# sfpp_conn.net
KiCad netlist of a schematic drawn in Altium Designer
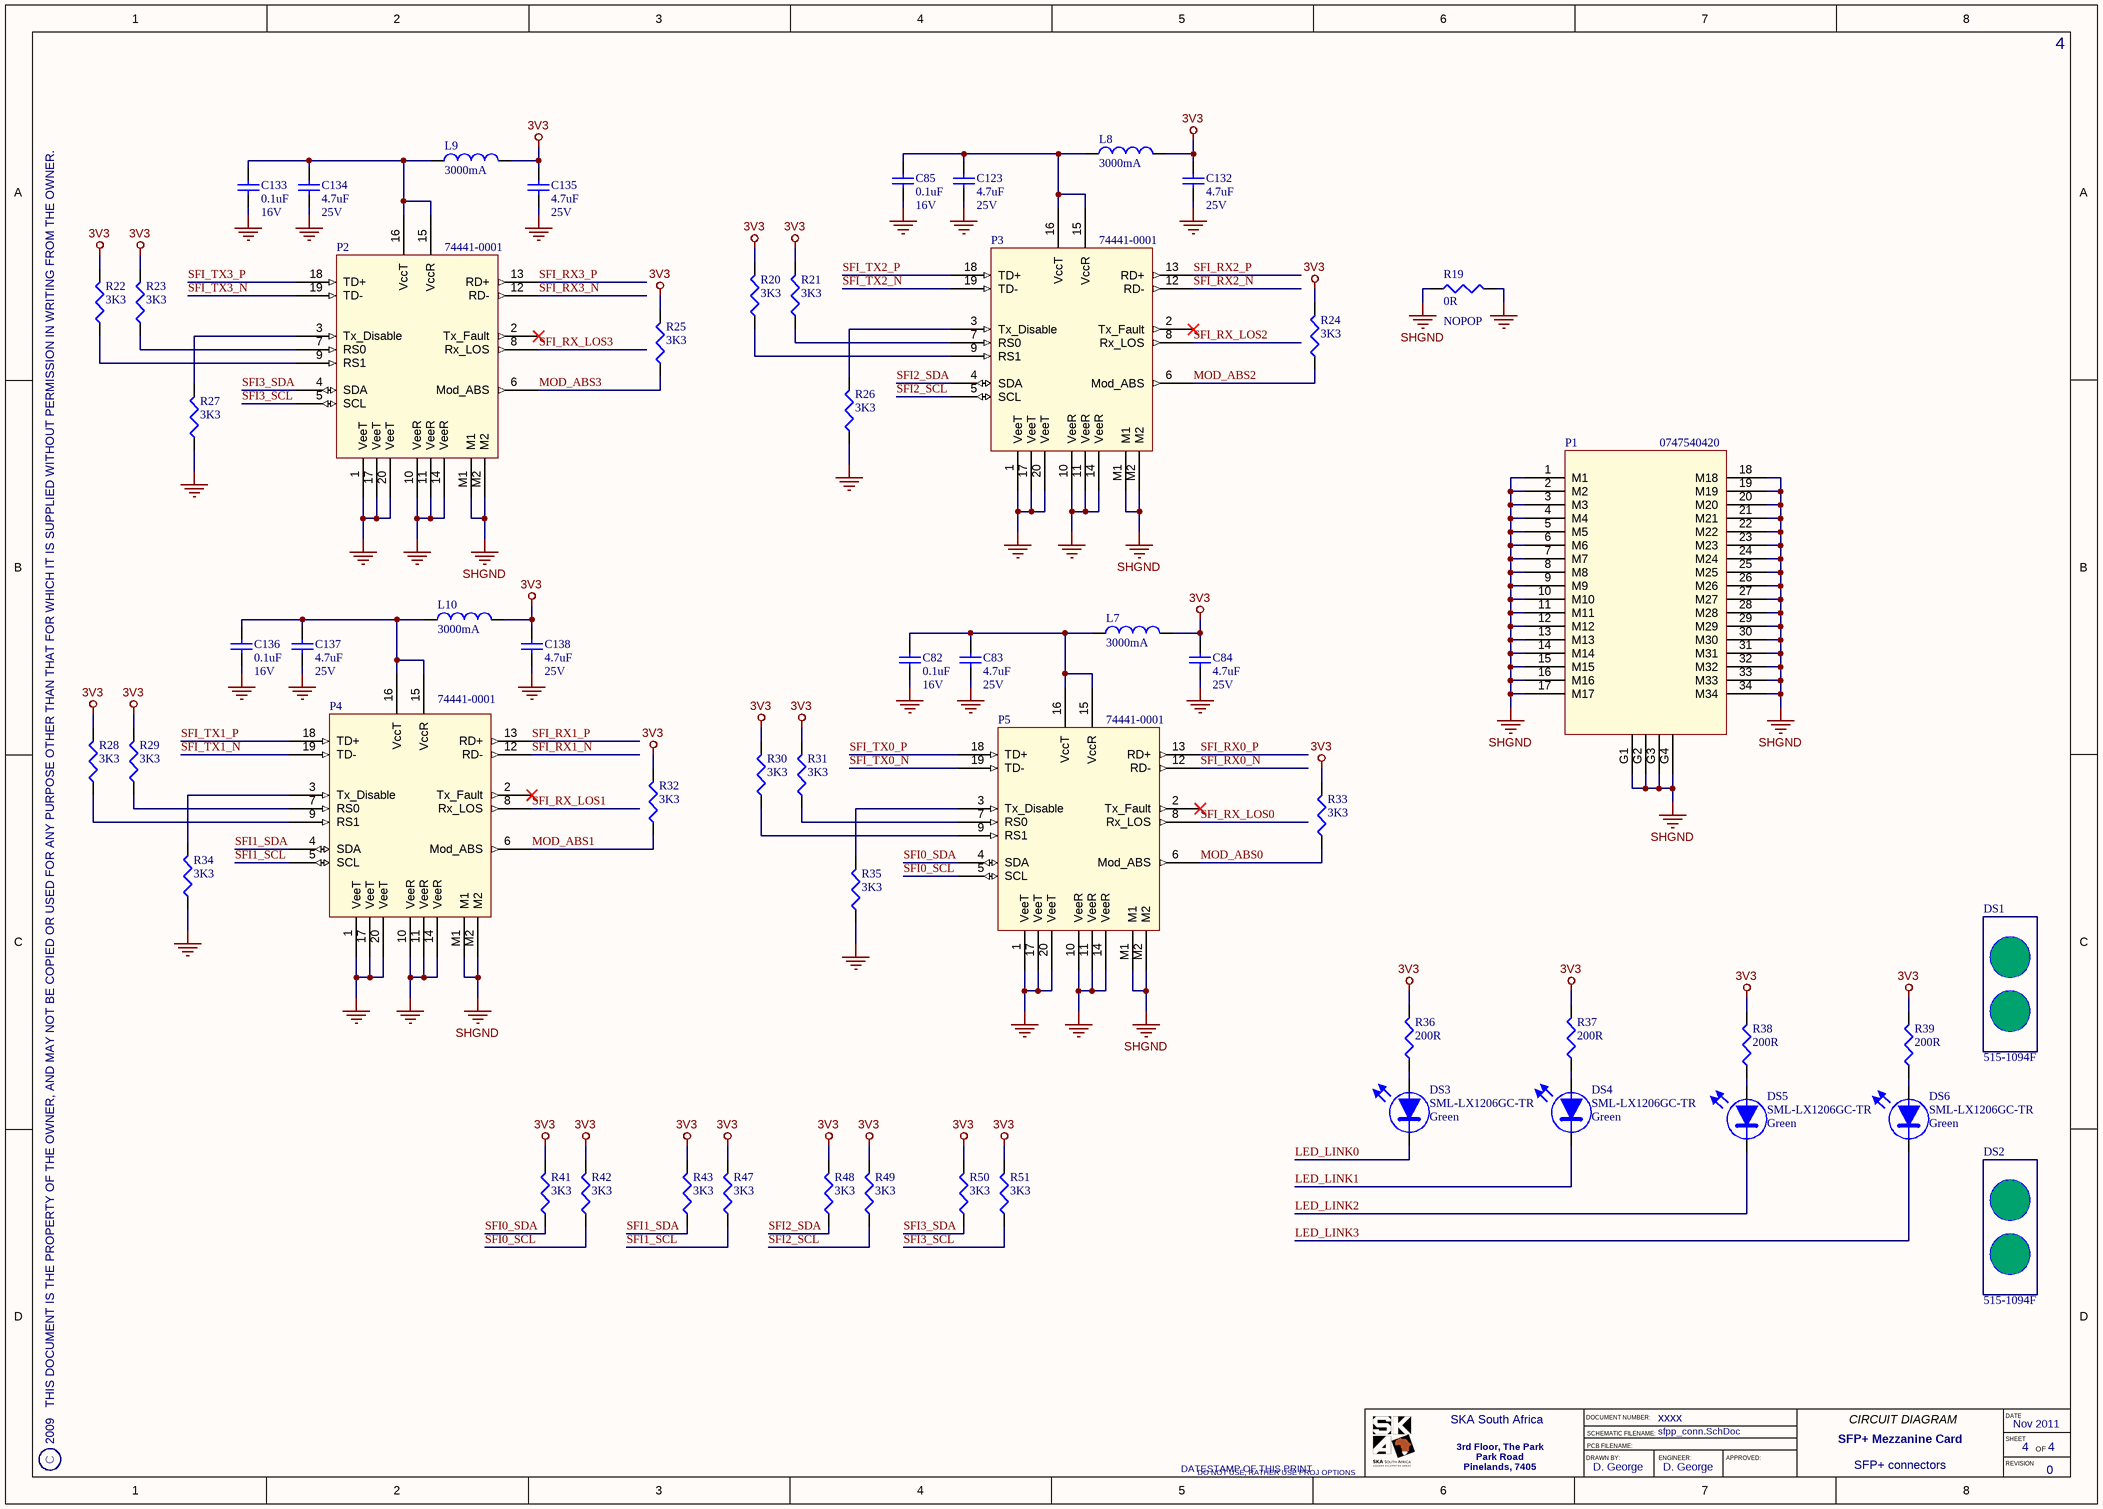
[diagram p0: sfpp_conn.SchDoc]

(export (version "E")
  (design (tool "Eeschema 10.0.6"))
  (components
    (comp (ref "C82")
      (value "0.1uF")
      (footprint "CAPC1005X60L")
      (description "0.1uF, Ceramic Capacitor")
      (fields
        (field (name "RATING") "16V")
        (field (name "MANUFACTURER") "VENKEL")
        (field (name "PARTNUM") "C0402X7R160-104KN")
      )
      (libsource (lib "altium_db") (part "CapStd"))
    )
    (comp (ref "C83")
      (value "4.7uF")
      (footprint "CAPC2012X127L")
      (description "4.7uF, Ceramic Capacitor")
      (fields
        (field (name "RATING") "25V")
        (field (name "MANUFACTURER") "MURATA")
        (field (name "PARTNUM") "GRM21BR61E475KA12K")
      )
      (libsource (lib "altium_db") (part "CapStd"))
    )
    (comp (ref "C84")
      (value "4.7uF")
      (footprint "CAPC2012X127L")
      (description "4.7uF, Ceramic Capacitor")
      (fields
        (field (name "RATING") "25V")
        (field (name "MANUFACTURER") "MURATA")
        (field (name "PARTNUM") "GRM21BR61E475KA12K")
      )
      (libsource (lib "altium_db") (part "CapStd"))
    )
    (comp (ref "C85")
      (value "0.1uF")
      (footprint "CAPC1005X60L")
      (description "0.1uF, Ceramic Capacitor")
      (fields
        (field (name "RATING") "16V")
        (field (name "MANUFACTURER") "VENKEL")
        (field (name "PARTNUM") "C0402X7R160-104KN")
      )
      (libsource (lib "altium_db") (part "CapStd"))
    )
    (comp (ref "C123")
      (value "4.7uF")
      (footprint "CAPC2012X127L")
      (description "4.7uF, Ceramic Capacitor")
      (fields
        (field (name "RATING") "25V")
        (field (name "MANUFACTURER") "MURATA")
        (field (name "PARTNUM") "GRM21BR61E475KA12K")
      )
      (libsource (lib "altium_db") (part "CapStd"))
    )
    (comp (ref "C132")
      (value "4.7uF")
      (footprint "CAPC2012X127L")
      (description "4.7uF, Ceramic Capacitor")
      (fields
        (field (name "RATING") "25V")
        (field (name "MANUFACTURER") "MURATA")
        (field (name "PARTNUM") "GRM21BR61E475KA12K")
      )
      (libsource (lib "altium_db") (part "CapStd"))
    )
    (comp (ref "C133")
      (value "0.1uF")
      (footprint "CAPC1005X60L")
      (description "0.1uF, Ceramic Capacitor")
      (fields
        (field (name "RATING") "16V")
        (field (name "MANUFACTURER") "VENKEL")
        (field (name "PARTNUM") "C0402X7R160-104KN")
      )
      (libsource (lib "altium_db") (part "CapStd"))
    )
    (comp (ref "C134")
      (value "4.7uF")
      (footprint "CAPC2012X127L")
      (description "4.7uF, Ceramic Capacitor")
      (fields
        (field (name "RATING") "25V")
        (field (name "MANUFACTURER") "MURATA")
        (field (name "PARTNUM") "GRM21BR61E475KA12K")
      )
      (libsource (lib "altium_db") (part "CapStd"))
    )
    (comp (ref "C135")
      (value "4.7uF")
      (footprint "CAPC2012X127L")
      (description "4.7uF, Ceramic Capacitor")
      (fields
        (field (name "RATING") "25V")
        (field (name "MANUFACTURER") "MURATA")
        (field (name "PARTNUM") "GRM21BR61E475KA12K")
      )
      (libsource (lib "altium_db") (part "CapStd"))
    )
    (comp (ref "C136")
      (value "0.1uF")
      (footprint "CAPC1005X60L")
      (description "0.1uF, Ceramic Capacitor")
      (fields
        (field (name "RATING") "16V")
        (field (name "MANUFACTURER") "VENKEL")
        (field (name "PARTNUM") "C0402X7R160-104KN")
      )
      (libsource (lib "altium_db") (part "CapStd"))
    )
    (comp (ref "C137")
      (value "4.7uF")
      (footprint "CAPC2012X127L")
      (description "4.7uF, Ceramic Capacitor")
      (fields
        (field (name "RATING") "25V")
        (field (name "MANUFACTURER") "MURATA")
        (field (name "PARTNUM") "GRM21BR61E475KA12K")
      )
      (libsource (lib "altium_db") (part "CapStd"))
    )
    (comp (ref "C138")
      (value "4.7uF")
      (footprint "CAPC2012X127L")
      (description "4.7uF, Ceramic Capacitor")
      (fields
        (field (name "RATING") "25V")
        (field (name "MANUFACTURER") "MURATA")
        (field (name "PARTNUM") "GRM21BR61E475KA12K")
      )
      (libsource (lib "altium_db") (part "CapStd"))
    )
    (comp (ref "DS1")
      (value "515-1094F")
      (footprint "DIALIGHT_515-1094F")
      (description "2-High, press-fit, 3mm round, light-pipe")
      (fields (field (name "MANUFACTURER") "Dialight"))
      (libsource (lib "altium_db") (part "LPIPE_2H"))
    )
    (comp (ref "DS2")
      (value "515-1094F")
      (footprint "DIALIGHT_515-1094F")
      (description "2-High, press-fit, 3mm round, light-pipe")
      (fields (field (name "MANUFACTURER") "Dialight"))
      (libsource (lib "altium_db") (part "LPIPE_2H"))
    )
    (comp (ref "DS3")
      (value "SML-LX1206GC-TR")
      (footprint "LEDC3216X120N")
      (description "Green, Surface mount, LED, 1206")
      (fields (field (name "COLOUR") "Green") (field (name "MANUFACTURER") "LUMEX"))
      (libsource (lib "altium_db") (part "LEDSTD"))
    )
    (comp (ref "DS4")
      (value "SML-LX1206GC-TR")
      (footprint "LEDC3216X120N")
      (description "Green, Surface mount, LED, 1206")
      (fields (field (name "COLOUR") "Green") (field (name "MANUFACTURER") "LUMEX"))
      (libsource (lib "altium_db") (part "LEDSTD"))
    )
    (comp (ref "DS5")
      (value "SML-LX1206GC-TR")
      (footprint "LEDC3216X120N")
      (description "Green, Surface mount, LED, 1206")
      (fields (field (name "COLOUR") "Green") (field (name "MANUFACTURER") "LUMEX"))
      (libsource (lib "altium_db") (part "LEDSTD"))
    )
    (comp (ref "DS6")
      (value "SML-LX1206GC-TR")
      (footprint "LEDC3216X120N")
      (description "Green, Surface mount, LED, 1206")
      (fields (field (name "COLOUR") "Green") (field (name "MANUFACTURER") "LUMEX"))
      (libsource (lib "altium_db") (part "LEDSTD"))
    )
    (comp (ref "L7")
      (value "120R")
      (footprint "INDC3216X130L")
      (description "120 Ohm, Chip Ferrite Brad")
      (fields
        (field (name "RATING") "3000mA")
        (field (name "MANUFACTURER") "Murata")
        (field (name "PARTNUM") "BLM31PG121SN1")
      )
      (libsource (lib "altium_db") (part "IndStd"))
    )
    (comp (ref "L8")
      (value "120R")
      (footprint "INDC3216X130L")
      (description "120 Ohm, Chip Ferrite Brad")
      (fields
        (field (name "RATING") "3000mA")
        (field (name "MANUFACTURER") "Murata")
        (field (name "PARTNUM") "BLM31PG121SN1")
      )
      (libsource (lib "altium_db") (part "IndStd"))
    )
    (comp (ref "L9")
      (value "120R")
      (footprint "INDC3216X130L")
      (description "120 Ohm, Chip Ferrite Brad")
      (fields
        (field (name "RATING") "3000mA")
        (field (name "MANUFACTURER") "Murata")
        (field (name "PARTNUM") "BLM31PG121SN1")
      )
      (libsource (lib "altium_db") (part "IndStd"))
    )
    (comp (ref "L10")
      (value "120R")
      (footprint "INDC3216X130L")
      (description "120 Ohm, Chip Ferrite Brad")
      (fields
        (field (name "RATING") "3000mA")
        (field (name "MANUFACTURER") "Murata")
        (field (name "PARTNUM") "BLM31PG121SN1")
      )
      (libsource (lib "altium_db") (part "IndStd"))
    )
    (comp (ref "P1")
      (value "0747540420")
      (footprint "MOLEX_0747540420")
      (description "SFP+ 1X4 Cage Assembly")
      (fields (field (name "PARTNUM") "0747540420") (field (name "MANUFACTURER") "Molex"))
      (libsource (lib "altium_db") (part "MOLEX_0747540420"))
    )
    (comp (ref "P2")
      (value "74441-0001")
      (footprint "MOLEX_74441-0001")
      (description "20 Circuit, 0.8mm pitch SFP+ host connector")
      (fields (field (name "PARTNUM") "74441-0001") (field (name "MANUFACTURER") "Molex"))
      (libsource (lib "altium_db") (part "MOLEX_74441-0001"))
    )
    (comp (ref "P3")
      (value "74441-0001")
      (footprint "MOLEX_74441-0001")
      (description "20 Circuit, 0.8mm pitch SFP+ host connector")
      (fields (field (name "PARTNUM") "74441-0001") (field (name "MANUFACTURER") "Molex"))
      (libsource (lib "altium_db") (part "MOLEX_74441-0001"))
    )
    (comp (ref "P4")
      (value "74441-0001")
      (footprint "MOLEX_74441-0001")
      (description "20 Circuit, 0.8mm pitch SFP+ host connector")
      (fields (field (name "PARTNUM") "74441-0001") (field (name "MANUFACTURER") "Molex"))
      (libsource (lib "altium_db") (part "MOLEX_74441-0001"))
    )
    (comp (ref "P5")
      (value "74441-0001")
      (footprint "MOLEX_74441-0001")
      (description "20 Circuit, 0.8mm pitch SFP+ host connector")
      (fields (field (name "PARTNUM") "74441-0001") (field (name "MANUFACTURER") "Molex"))
      (libsource (lib "altium_db") (part "MOLEX_74441-0001"))
    )
    (comp (ref "R19")
      (value "0R")
      (footprint "RESC1005X40L")
      (description "0R, 1.1mm x 0.5mm, Thick Film Resistor")
      (fields (field (name "MANUFACTURER") "ROYALOHM") (field (name "PARTNUM") "0402WG00000T1E"))
      (libsource (lib "altium_db") (part "ResStd"))
    )
    (comp (ref "R20")
      (value "3K3")
      (footprint "RESC1005X40L")
      (description "3K3, 1.1mm x 0.5mm, Thick Film Resistor")
      (fields (field (name "MANUFACTURER") "ROYALOHM") (field (name "PARTNUM") "0402WGJ0332T1E"))
      (libsource (lib "altium_db") (part "ResStd"))
    )
    (comp (ref "R21")
      (value "3K3")
      (footprint "RESC1005X40L")
      (description "3K3, 1.1mm x 0.5mm, Thick Film Resistor")
      (fields (field (name "MANUFACTURER") "ROYALOHM") (field (name "PARTNUM") "0402WGJ0332T1E"))
      (libsource (lib "altium_db") (part "ResStd"))
    )
    (comp (ref "R22")
      (value "3K3")
      (footprint "RESC1005X40L")
      (description "3K3, 1.1mm x 0.5mm, Thick Film Resistor")
      (fields (field (name "MANUFACTURER") "ROYALOHM") (field (name "PARTNUM") "0402WGJ0332T1E"))
      (libsource (lib "altium_db") (part "ResStd"))
    )
    (comp (ref "R23")
      (value "3K3")
      (footprint "RESC1005X40L")
      (description "3K3, 1.1mm x 0.5mm, Thick Film Resistor")
      (fields (field (name "MANUFACTURER") "ROYALOHM") (field (name "PARTNUM") "0402WGJ0332T1E"))
      (libsource (lib "altium_db") (part "ResStd"))
    )
    (comp (ref "R24")
      (value "3K3")
      (footprint "RESC1005X40L")
      (description "3K3, 1.1mm x 0.5mm, Thick Film Resistor")
      (fields (field (name "MANUFACTURER") "ROYALOHM") (field (name "PARTNUM") "0402WGJ0332T1E"))
      (libsource (lib "altium_db") (part "ResStd"))
    )
    (comp (ref "R25")
      (value "3K3")
      (footprint "RESC1005X40L")
      (description "3K3, 1.1mm x 0.5mm, Thick Film Resistor")
      (fields (field (name "MANUFACTURER") "ROYALOHM") (field (name "PARTNUM") "0402WGJ0332T1E"))
      (libsource (lib "altium_db") (part "ResStd"))
    )
    (comp (ref "R26")
      (value "3K3")
      (footprint "RESC1005X40L")
      (description "3K3, 1.1mm x 0.5mm, Thick Film Resistor")
      (fields (field (name "MANUFACTURER") "ROYALOHM") (field (name "PARTNUM") "0402WGJ0332T1E"))
      (libsource (lib "altium_db") (part "ResStd"))
    )
    (comp (ref "R27")
      (value "3K3")
      (footprint "RESC1005X40L")
      (description "3K3, 1.1mm x 0.5mm, Thick Film Resistor")
      (fields (field (name "MANUFACTURER") "ROYALOHM") (field (name "PARTNUM") "0402WGJ0332T1E"))
      (libsource (lib "altium_db") (part "ResStd"))
    )
    (comp (ref "R28")
      (value "3K3")
      (footprint "RESC1005X40L")
      (description "3K3, 1.1mm x 0.5mm, Thick Film Resistor")
      (fields (field (name "MANUFACTURER") "ROYALOHM") (field (name "PARTNUM") "0402WGJ0332T1E"))
      (libsource (lib "altium_db") (part "ResStd"))
    )
    (comp (ref "R29")
      (value "3K3")
      (footprint "RESC1005X40L")
      (description "3K3, 1.1mm x 0.5mm, Thick Film Resistor")
      (fields (field (name "MANUFACTURER") "ROYALOHM") (field (name "PARTNUM") "0402WGJ0332T1E"))
      (libsource (lib "altium_db") (part "ResStd"))
    )
    (comp (ref "R30")
      (value "3K3")
      (footprint "RESC1005X40L")
      (description "3K3, 1.1mm x 0.5mm, Thick Film Resistor")
      (fields (field (name "MANUFACTURER") "ROYALOHM") (field (name "PARTNUM") "0402WGJ0332T1E"))
      (libsource (lib "altium_db") (part "ResStd"))
    )
    (comp (ref "R31")
      (value "3K3")
      (footprint "RESC1005X40L")
      (description "3K3, 1.1mm x 0.5mm, Thick Film Resistor")
      (fields (field (name "MANUFACTURER") "ROYALOHM") (field (name "PARTNUM") "0402WGJ0332T1E"))
      (libsource (lib "altium_db") (part "ResStd"))
    )
    (comp (ref "R32")
      (value "3K3")
      (footprint "RESC1005X40L")
      (description "3K3, 1.1mm x 0.5mm, Thick Film Resistor")
      (fields (field (name "MANUFACTURER") "ROYALOHM") (field (name "PARTNUM") "0402WGJ0332T1E"))
      (libsource (lib "altium_db") (part "ResStd"))
    )
    (comp (ref "R33")
      (value "3K3")
      (footprint "RESC1005X40L")
      (description "3K3, 1.1mm x 0.5mm, Thick Film Resistor")
      (fields (field (name "MANUFACTURER") "ROYALOHM") (field (name "PARTNUM") "0402WGJ0332T1E"))
      (libsource (lib "altium_db") (part "ResStd"))
    )
    (comp (ref "R34")
      (value "3K3")
      (footprint "RESC1005X40L")
      (description "3K3, 1.1mm x 0.5mm, Thick Film Resistor")
      (fields (field (name "MANUFACTURER") "ROYALOHM") (field (name "PARTNUM") "0402WGJ0332T1E"))
      (libsource (lib "altium_db") (part "ResStd"))
    )
    (comp (ref "R35")
      (value "3K3")
      (footprint "RESC1005X40L")
      (description "3K3, 1.1mm x 0.5mm, Thick Film Resistor")
      (fields (field (name "MANUFACTURER") "ROYALOHM") (field (name "PARTNUM") "0402WGJ0332T1E"))
      (libsource (lib "altium_db") (part "ResStd"))
    )
    (comp (ref "R36")
      (value "200R")
      (footprint "RESC1005X40L")
      (description "200R, 1.1mm x 0.5mm, Thick Film Resistor")
      (fields (field (name "MANUFACTURER") "ROYALOHM") (field (name "PARTNUM") "0402WGF0201T1E"))
      (libsource (lib "altium_db") (part "ResStd"))
    )
    (comp (ref "R37")
      (value "200R")
      (footprint "RESC1005X40L")
      (description "200R, 1.1mm x 0.5mm, Thick Film Resistor")
      (fields (field (name "MANUFACTURER") "ROYALOHM") (field (name "PARTNUM") "0402WGF0201T1E"))
      (libsource (lib "altium_db") (part "ResStd"))
    )
    (comp (ref "R38")
      (value "200R")
      (footprint "RESC1005X40L")
      (description "200R, 1.1mm x 0.5mm, Thick Film Resistor")
      (fields (field (name "MANUFACTURER") "ROYALOHM") (field (name "PARTNUM") "0402WGF0201T1E"))
      (libsource (lib "altium_db") (part "ResStd"))
    )
    (comp (ref "R39")
      (value "200R")
      (footprint "RESC1005X40L")
      (description "200R, 1.1mm x 0.5mm, Thick Film Resistor")
      (fields (field (name "MANUFACTURER") "ROYALOHM") (field (name "PARTNUM") "0402WGF0201T1E"))
      (libsource (lib "altium_db") (part "ResStd"))
    )
    (comp (ref "R41")
      (value "3K3")
      (footprint "RESC1005X40L")
      (description "3K3, 1.1mm x 0.5mm, Thick Film Resistor")
      (fields (field (name "MANUFACTURER") "ROYALOHM") (field (name "PARTNUM") "0402WGJ0332T1E"))
      (libsource (lib "altium_db") (part "ResStd"))
    )
    (comp (ref "R42")
      (value "3K3")
      (footprint "RESC1005X40L")
      (description "3K3, 1.1mm x 0.5mm, Thick Film Resistor")
      (fields (field (name "MANUFACTURER") "ROYALOHM") (field (name "PARTNUM") "0402WGJ0332T1E"))
      (libsource (lib "altium_db") (part "ResStd"))
    )
    (comp (ref "R43")
      (value "3K3")
      (footprint "RESC1005X40L")
      (description "3K3, 1.1mm x 0.5mm, Thick Film Resistor")
      (fields (field (name "MANUFACTURER") "ROYALOHM") (field (name "PARTNUM") "0402WGJ0332T1E"))
      (libsource (lib "altium_db") (part "ResStd"))
    )
    (comp (ref "R47")
      (value "3K3")
      (footprint "RESC1005X40L")
      (description "3K3, 1.1mm x 0.5mm, Thick Film Resistor")
      (fields (field (name "MANUFACTURER") "ROYALOHM") (field (name "PARTNUM") "0402WGJ0332T1E"))
      (libsource (lib "altium_db") (part "ResStd"))
    )
    (comp (ref "R48")
      (value "3K3")
      (footprint "RESC1005X40L")
      (description "3K3, 1.1mm x 0.5mm, Thick Film Resistor")
      (fields (field (name "MANUFACTURER") "ROYALOHM") (field (name "PARTNUM") "0402WGJ0332T1E"))
      (libsource (lib "altium_db") (part "ResStd"))
    )
    (comp (ref "R49")
      (value "3K3")
      (footprint "RESC1005X40L")
      (description "3K3, 1.1mm x 0.5mm, Thick Film Resistor")
      (fields (field (name "MANUFACTURER") "ROYALOHM") (field (name "PARTNUM") "0402WGJ0332T1E"))
      (libsource (lib "altium_db") (part "ResStd"))
    )
    (comp (ref "R50")
      (value "3K3")
      (footprint "RESC1005X40L")
      (description "3K3, 1.1mm x 0.5mm, Thick Film Resistor")
      (fields (field (name "MANUFACTURER") "ROYALOHM") (field (name "PARTNUM") "0402WGJ0332T1E"))
      (libsource (lib "altium_db") (part "ResStd"))
    )
    (comp (ref "R51")
      (value "3K3")
      (footprint "RESC1005X40L")
      (description "3K3, 1.1mm x 0.5mm, Thick Film Resistor")
      (fields (field (name "MANUFACTURER") "ROYALOHM") (field (name "PARTNUM") "0402WGJ0332T1E"))
      (libsource (lib "altium_db") (part "ResStd"))
    )
  )
  (nets
    (net (code "1") (name "/LED_LINK0") (class "Default")
      (node (ref "DS3") (pin "1") (pinfunction "K_1") (pintype "passive"))
    )
    (net (code "2") (name "/LED_LINK1") (class "Default")
      (node (ref "DS4") (pin "1") (pinfunction "K_1") (pintype "passive"))
    )
    (net (code "3") (name "/LED_LINK2") (class "Default")
      (node (ref "DS5") (pin "1") (pinfunction "K_1") (pintype "passive"))
    )
    (net (code "4") (name "/LED_LINK3") (class "Default")
      (node (ref "DS6") (pin "1") (pinfunction "K_1") (pintype "passive"))
    )
    (net (code "5") (name "/MOD_ABS0") (class "Default")
      (node (ref "P5") (pin "6") (pinfunction "Mod_ABS_6") (pintype "output"))
      (node (ref "R33") (pin "1") (pinfunction "1_1") (pintype "passive"))
    )
    (net (code "6") (name "/MOD_ABS1") (class "Default")
      (node (ref "P4") (pin "6") (pinfunction "Mod_ABS_6") (pintype "output"))
      (node (ref "R32") (pin "1") (pinfunction "1_1") (pintype "passive"))
    )
    (net (code "7") (name "/MOD_ABS2") (class "Default")
      (node (ref "P3") (pin "6") (pinfunction "Mod_ABS_6") (pintype "output"))
      (node (ref "R24") (pin "1") (pinfunction "1_1") (pintype "passive"))
    )
    (net (code "8") (name "/MOD_ABS3") (class "Default")
      (node (ref "P2") (pin "6") (pinfunction "Mod_ABS_6") (pintype "output"))
      (node (ref "R25") (pin "1") (pinfunction "1_1") (pintype "passive"))
    )
    (net (code "9") (name "/SFI0_SCL") (class "Default")
      (node (ref "P5") (pin "5") (pinfunction "SCL_5") (pintype "bidirectional"))
      (node (ref "R42") (pin "1") (pinfunction "1_1") (pintype "passive"))
    )
    (net (code "10") (name "/SFI0_SDA") (class "Default")
      (node (ref "P5") (pin "4") (pinfunction "SDA_4") (pintype "bidirectional"))
      (node (ref "R41") (pin "1") (pinfunction "1_1") (pintype "passive"))
    )
    (net (code "11") (name "/SFI1_SCL") (class "Default")
      (node (ref "P4") (pin "5") (pinfunction "SCL_5") (pintype "bidirectional"))
      (node (ref "R47") (pin "1") (pinfunction "1_1") (pintype "passive"))
    )
    (net (code "12") (name "/SFI1_SDA") (class "Default")
      (node (ref "P4") (pin "4") (pinfunction "SDA_4") (pintype "bidirectional"))
      (node (ref "R43") (pin "1") (pinfunction "1_1") (pintype "passive"))
    )
    (net (code "13") (name "/SFI2_SCL") (class "Default")
      (node (ref "P3") (pin "5") (pinfunction "SCL_5") (pintype "bidirectional"))
      (node (ref "R49") (pin "1") (pinfunction "1_1") (pintype "passive"))
    )
    (net (code "14") (name "/SFI2_SDA") (class "Default")
      (node (ref "P3") (pin "4") (pinfunction "SDA_4") (pintype "bidirectional"))
      (node (ref "R48") (pin "1") (pinfunction "1_1") (pintype "passive"))
    )
    (net (code "15") (name "/SFI3_SCL") (class "Default")
      (node (ref "P2") (pin "5") (pinfunction "SCL_5") (pintype "bidirectional"))
      (node (ref "R51") (pin "1") (pinfunction "1_1") (pintype "passive"))
    )
    (net (code "16") (name "/SFI3_SDA") (class "Default")
      (node (ref "P2") (pin "4") (pinfunction "SDA_4") (pintype "bidirectional"))
      (node (ref "R50") (pin "1") (pinfunction "1_1") (pintype "passive"))
    )
    (net (code "17") (name "/SFI_RX0_N") (class "Default")
      (node (ref "P5") (pin "12") (pinfunction "RD-_12") (pintype "output"))
    )
    (net (code "18") (name "/SFI_RX0_P") (class "Default")
      (node (ref "P5") (pin "13") (pinfunction "RD+_13") (pintype "output"))
    )
    (net (code "19") (name "/SFI_RX1_N") (class "Default")
      (node (ref "P4") (pin "12") (pinfunction "RD-_12") (pintype "output"))
    )
    (net (code "20") (name "/SFI_RX1_P") (class "Default")
      (node (ref "P4") (pin "13") (pinfunction "RD+_13") (pintype "output"))
    )
    (net (code "21") (name "/SFI_RX2_N") (class "Default")
      (node (ref "P3") (pin "12") (pinfunction "RD-_12") (pintype "output"))
    )
    (net (code "22") (name "/SFI_RX2_P") (class "Default")
      (node (ref "P3") (pin "13") (pinfunction "RD+_13") (pintype "output"))
    )
    (net (code "23") (name "/SFI_RX3_N") (class "Default")
      (node (ref "P2") (pin "12") (pinfunction "RD-_12") (pintype "output"))
    )
    (net (code "24") (name "/SFI_RX3_P") (class "Default")
      (node (ref "P2") (pin "13") (pinfunction "RD+_13") (pintype "output"))
    )
    (net (code "25") (name "/SFI_RX_LOS0") (class "Default")
      (node (ref "P5") (pin "8") (pinfunction "Rx_LOS_8") (pintype "output"))
    )
    (net (code "26") (name "/SFI_RX_LOS1") (class "Default")
      (node (ref "P4") (pin "8") (pinfunction "Rx_LOS_8") (pintype "output"))
    )
    (net (code "27") (name "/SFI_RX_LOS2") (class "Default")
      (node (ref "P3") (pin "8") (pinfunction "Rx_LOS_8") (pintype "output"))
    )
    (net (code "28") (name "/SFI_RX_LOS3") (class "Default")
      (node (ref "P2") (pin "8") (pinfunction "Rx_LOS_8") (pintype "output"))
    )
    (net (code "29") (name "/SFI_TX0_N") (class "Default")
      (node (ref "P5") (pin "19") (pinfunction "TD-_19") (pintype "input"))
    )
    (net (code "30") (name "/SFI_TX0_P") (class "Default")
      (node (ref "P5") (pin "18") (pinfunction "TD+_18") (pintype "input"))
    )
    (net (code "31") (name "/SFI_TX1_N") (class "Default")
      (node (ref "P4") (pin "19") (pinfunction "TD-_19") (pintype "input"))
    )
    (net (code "32") (name "/SFI_TX1_P") (class "Default")
      (node (ref "P4") (pin "18") (pinfunction "TD+_18") (pintype "input"))
    )
    (net (code "33") (name "/SFI_TX2_N") (class "Default")
      (node (ref "P3") (pin "19") (pinfunction "TD-_19") (pintype "input"))
    )
    (net (code "34") (name "/SFI_TX2_P") (class "Default")
      (node (ref "P3") (pin "18") (pinfunction "TD+_18") (pintype "input"))
    )
    (net (code "35") (name "/SFI_TX3_N") (class "Default")
      (node (ref "P2") (pin "19") (pinfunction "TD-_19") (pintype "input"))
    )
    (net (code "36") (name "/SFI_TX3_P") (class "Default")
      (node (ref "P2") (pin "18") (pinfunction "TD+_18") (pintype "input"))
    )
    (net (code "37") (name "3V3") (class "Default")
      (node (ref "C132") (pin "2") (pinfunction "2_2") (pintype "passive"))
      (node (ref "C135") (pin "2") (pinfunction "2_2") (pintype "passive"))
      (node (ref "C138") (pin "2") (pinfunction "2_2") (pintype "passive"))
      (node (ref "C84") (pin "2") (pinfunction "2_2") (pintype "passive"))
      (node (ref "L10") (pin "2") (pinfunction "2_2") (pintype "passive"))
      (node (ref "L7") (pin "2") (pinfunction "2_2") (pintype "passive"))
      (node (ref "L8") (pin "2") (pinfunction "2_2") (pintype "passive"))
      (node (ref "L9") (pin "2") (pinfunction "2_2") (pintype "passive"))
      (node (ref "R20") (pin "2") (pinfunction "2_2") (pintype "passive"))
      (node (ref "R21") (pin "2") (pinfunction "2_2") (pintype "passive"))
      (node (ref "R22") (pin "2") (pinfunction "2_2") (pintype "passive"))
      (node (ref "R23") (pin "2") (pinfunction "2_2") (pintype "passive"))
      (node (ref "R24") (pin "2") (pinfunction "2_2") (pintype "passive"))
      (node (ref "R25") (pin "2") (pinfunction "2_2") (pintype "passive"))
      (node (ref "R28") (pin "2") (pinfunction "2_2") (pintype "passive"))
      (node (ref "R29") (pin "2") (pinfunction "2_2") (pintype "passive"))
      (node (ref "R30") (pin "2") (pinfunction "2_2") (pintype "passive"))
      (node (ref "R31") (pin "2") (pinfunction "2_2") (pintype "passive"))
      (node (ref "R32") (pin "2") (pinfunction "2_2") (pintype "passive"))
      (node (ref "R33") (pin "2") (pinfunction "2_2") (pintype "passive"))
      (node (ref "R36") (pin "2") (pinfunction "2_2") (pintype "passive"))
      (node (ref "R37") (pin "2") (pinfunction "2_2") (pintype "passive"))
      (node (ref "R38") (pin "2") (pinfunction "2_2") (pintype "passive"))
      (node (ref "R39") (pin "2") (pinfunction "2_2") (pintype "passive"))
      (node (ref "R41") (pin "2") (pinfunction "2_2") (pintype "passive"))
      (node (ref "R42") (pin "2") (pinfunction "2_2") (pintype "passive"))
      (node (ref "R43") (pin "2") (pinfunction "2_2") (pintype "passive"))
      (node (ref "R47") (pin "2") (pinfunction "2_2") (pintype "passive"))
      (node (ref "R48") (pin "2") (pinfunction "2_2") (pintype "passive"))
      (node (ref "R49") (pin "2") (pinfunction "2_2") (pintype "passive"))
      (node (ref "R50") (pin "2") (pinfunction "2_2") (pintype "passive"))
      (node (ref "R51") (pin "2") (pinfunction "2_2") (pintype "passive"))
    )
    (net (code "38") (name "GND") (class "Default")
      (node (ref "C123") (pin "1") (pinfunction "1_1") (pintype "passive"))
      (node (ref "C132") (pin "1") (pinfunction "1_1") (pintype "passive"))
      (node (ref "C133") (pin "1") (pinfunction "1_1") (pintype "passive"))
      (node (ref "C134") (pin "1") (pinfunction "1_1") (pintype "passive"))
      (node (ref "C135") (pin "1") (pinfunction "1_1") (pintype "passive"))
      (node (ref "C136") (pin "1") (pinfunction "1_1") (pintype "passive"))
      (node (ref "C137") (pin "1") (pinfunction "1_1") (pintype "passive"))
      (node (ref "C138") (pin "1") (pinfunction "1_1") (pintype "passive"))
      (node (ref "C82") (pin "1") (pinfunction "1_1") (pintype "passive"))
      (node (ref "C83") (pin "1") (pinfunction "1_1") (pintype "passive"))
      (node (ref "C84") (pin "1") (pinfunction "1_1") (pintype "passive"))
      (node (ref "C85") (pin "1") (pinfunction "1_1") (pintype "passive"))
      (node (ref "P2") (pin "1") (pinfunction "VeeT_1") (pintype "power_in"))
      (node (ref "P2") (pin "10") (pinfunction "VeeR_10") (pintype "power_in"))
      (node (ref "P2") (pin "11") (pinfunction "VeeR_11") (pintype "power_in"))
      (node (ref "P2") (pin "14") (pinfunction "VeeR_14") (pintype "power_in"))
      (node (ref "P2") (pin "17") (pinfunction "VeeT_17") (pintype "power_in"))
      (node (ref "P2") (pin "20") (pinfunction "VeeT_20") (pintype "power_in"))
      (node (ref "P3") (pin "1") (pinfunction "VeeT_1") (pintype "power_in"))
      (node (ref "P3") (pin "10") (pinfunction "VeeR_10") (pintype "power_in"))
      (node (ref "P3") (pin "11") (pinfunction "VeeR_11") (pintype "power_in"))
      (node (ref "P3") (pin "14") (pinfunction "VeeR_14") (pintype "power_in"))
      (node (ref "P3") (pin "17") (pinfunction "VeeT_17") (pintype "power_in"))
      (node (ref "P3") (pin "20") (pinfunction "VeeT_20") (pintype "power_in"))
      (node (ref "P4") (pin "1") (pinfunction "VeeT_1") (pintype "power_in"))
      (node (ref "P4") (pin "10") (pinfunction "VeeR_10") (pintype "power_in"))
      (node (ref "P4") (pin "11") (pinfunction "VeeR_11") (pintype "power_in"))
      (node (ref "P4") (pin "14") (pinfunction "VeeR_14") (pintype "power_in"))
      (node (ref "P4") (pin "17") (pinfunction "VeeT_17") (pintype "power_in"))
      (node (ref "P4") (pin "20") (pinfunction "VeeT_20") (pintype "power_in"))
      (node (ref "P5") (pin "1") (pinfunction "VeeT_1") (pintype "power_in"))
      (node (ref "P5") (pin "10") (pinfunction "VeeR_10") (pintype "power_in"))
      (node (ref "P5") (pin "11") (pinfunction "VeeR_11") (pintype "power_in"))
      (node (ref "P5") (pin "14") (pinfunction "VeeR_14") (pintype "power_in"))
      (node (ref "P5") (pin "17") (pinfunction "VeeT_17") (pintype "power_in"))
      (node (ref "P5") (pin "20") (pinfunction "VeeT_20") (pintype "power_in"))
      (node (ref "R19") (pin "2") (pinfunction "2_2") (pintype "passive"))
      (node (ref "R26") (pin "1") (pinfunction "1_1") (pintype "passive"))
      (node (ref "R27") (pin "1") (pinfunction "1_1") (pintype "passive"))
      (node (ref "R34") (pin "1") (pinfunction "1_1") (pintype "passive"))
      (node (ref "R35") (pin "1") (pinfunction "1_1") (pintype "passive"))
    )
    (net (code "39") (name "Net-(DS3-A)") (class "Default")
      (node (ref "DS3") (pin "2") (pinfunction "A_2") (pintype "passive"))
      (node (ref "R36") (pin "1") (pinfunction "1_1") (pintype "passive"))
    )
    (net (code "40") (name "Net-(DS4-A)") (class "Default")
      (node (ref "DS4") (pin "2") (pinfunction "A_2") (pintype "passive"))
      (node (ref "R37") (pin "1") (pinfunction "1_1") (pintype "passive"))
    )
    (net (code "41") (name "Net-(DS5-A)") (class "Default")
      (node (ref "DS5") (pin "2") (pinfunction "A_2") (pintype "passive"))
      (node (ref "R38") (pin "1") (pinfunction "1_1") (pintype "passive"))
    )
    (net (code "42") (name "Net-(DS6-A)") (class "Default")
      (node (ref "DS6") (pin "2") (pinfunction "A_2") (pintype "passive"))
      (node (ref "R39") (pin "1") (pinfunction "1_1") (pintype "passive"))
    )
    (net (code "43") (name "Net-(P2-RS0)") (class "Default")
      (node (ref "P2") (pin "7") (pinfunction "RS0_7") (pintype "input"))
      (node (ref "R23") (pin "1") (pinfunction "1_1") (pintype "passive"))
    )
    (net (code "44") (name "Net-(P2-RS1)") (class "Default")
      (node (ref "P2") (pin "9") (pinfunction "RS1_9") (pintype "input"))
      (node (ref "R22") (pin "1") (pinfunction "1_1") (pintype "passive"))
    )
    (net (code "45") (name "Net-(P2-Tx_Disable)") (class "Default")
      (node (ref "P2") (pin "3") (pinfunction "Tx_Disable_3") (pintype "input"))
      (node (ref "R27") (pin "2") (pinfunction "2_2") (pintype "passive"))
    )
    (net (code "46") (name "Net-(P2-VccR)") (class "Default")
      (node (ref "C133") (pin "2") (pinfunction "2_2") (pintype "passive"))
      (node (ref "C134") (pin "2") (pinfunction "2_2") (pintype "passive"))
      (node (ref "L9") (pin "1") (pinfunction "1_1") (pintype "passive"))
      (node (ref "P2") (pin "15") (pinfunction "VccR_15") (pintype "power_in"))
      (node (ref "P2") (pin "16") (pinfunction "VccT_16") (pintype "power_in"))
    )
    (net (code "47") (name "Net-(P3-RS0)") (class "Default")
      (node (ref "P3") (pin "7") (pinfunction "RS0_7") (pintype "input"))
      (node (ref "R21") (pin "1") (pinfunction "1_1") (pintype "passive"))
    )
    (net (code "48") (name "Net-(P3-RS1)") (class "Default")
      (node (ref "P3") (pin "9") (pinfunction "RS1_9") (pintype "input"))
      (node (ref "R20") (pin "1") (pinfunction "1_1") (pintype "passive"))
    )
    (net (code "49") (name "Net-(P3-Tx_Disable)") (class "Default")
      (node (ref "P3") (pin "3") (pinfunction "Tx_Disable_3") (pintype "input"))
      (node (ref "R26") (pin "2") (pinfunction "2_2") (pintype "passive"))
    )
    (net (code "50") (name "Net-(P3-VccR)") (class "Default")
      (node (ref "C123") (pin "2") (pinfunction "2_2") (pintype "passive"))
      (node (ref "C85") (pin "2") (pinfunction "2_2") (pintype "passive"))
      (node (ref "L8") (pin "1") (pinfunction "1_1") (pintype "passive"))
      (node (ref "P3") (pin "15") (pinfunction "VccR_15") (pintype "power_in"))
      (node (ref "P3") (pin "16") (pinfunction "VccT_16") (pintype "power_in"))
    )
    (net (code "51") (name "Net-(P4-RS0)") (class "Default")
      (node (ref "P4") (pin "7") (pinfunction "RS0_7") (pintype "input"))
      (node (ref "R29") (pin "1") (pinfunction "1_1") (pintype "passive"))
    )
    (net (code "52") (name "Net-(P4-RS1)") (class "Default")
      (node (ref "P4") (pin "9") (pinfunction "RS1_9") (pintype "input"))
      (node (ref "R28") (pin "1") (pinfunction "1_1") (pintype "passive"))
    )
    (net (code "53") (name "Net-(P4-Tx_Disable)") (class "Default")
      (node (ref "P4") (pin "3") (pinfunction "Tx_Disable_3") (pintype "input"))
      (node (ref "R34") (pin "2") (pinfunction "2_2") (pintype "passive"))
    )
    (net (code "54") (name "Net-(P4-VccR)") (class "Default")
      (node (ref "C136") (pin "2") (pinfunction "2_2") (pintype "passive"))
      (node (ref "C137") (pin "2") (pinfunction "2_2") (pintype "passive"))
      (node (ref "L10") (pin "1") (pinfunction "1_1") (pintype "passive"))
      (node (ref "P4") (pin "15") (pinfunction "VccR_15") (pintype "power_in"))
      (node (ref "P4") (pin "16") (pinfunction "VccT_16") (pintype "power_in"))
    )
    (net (code "55") (name "Net-(P5-RS0)") (class "Default")
      (node (ref "P5") (pin "7") (pinfunction "RS0_7") (pintype "input"))
      (node (ref "R31") (pin "1") (pinfunction "1_1") (pintype "passive"))
    )
    (net (code "56") (name "Net-(P5-RS1)") (class "Default")
      (node (ref "P5") (pin "9") (pinfunction "RS1_9") (pintype "input"))
      (node (ref "R30") (pin "1") (pinfunction "1_1") (pintype "passive"))
    )
    (net (code "57") (name "Net-(P5-Tx_Disable)") (class "Default")
      (node (ref "P5") (pin "3") (pinfunction "Tx_Disable_3") (pintype "input"))
      (node (ref "R35") (pin "2") (pinfunction "2_2") (pintype "passive"))
    )
    (net (code "58") (name "Net-(P5-VccR)") (class "Default")
      (node (ref "C82") (pin "2") (pinfunction "2_2") (pintype "passive"))
      (node (ref "C83") (pin "2") (pinfunction "2_2") (pintype "passive"))
      (node (ref "L7") (pin "1") (pinfunction "1_1") (pintype "passive"))
      (node (ref "P5") (pin "15") (pinfunction "VccR_15") (pintype "power_in"))
      (node (ref "P5") (pin "16") (pinfunction "VccT_16") (pintype "power_in"))
    )
    (net (code "59") (name "SHGND") (class "Default")
      (node (ref "P1") (pin "1") (pinfunction "M1_1") (pintype "power_in"))
      (node (ref "P1") (pin "10") (pinfunction "M10_10") (pintype "power_in"))
      (node (ref "P1") (pin "11") (pinfunction "M11_11") (pintype "power_in"))
      (node (ref "P1") (pin "12") (pinfunction "M12_12") (pintype "power_in"))
      (node (ref "P1") (pin "13") (pinfunction "M13_13") (pintype "power_in"))
      (node (ref "P1") (pin "14") (pinfunction "M14_14") (pintype "power_in"))
      (node (ref "P1") (pin "15") (pinfunction "M15_15") (pintype "power_in"))
      (node (ref "P1") (pin "16") (pinfunction "M16_16") (pintype "power_in"))
      (node (ref "P1") (pin "17") (pinfunction "M17_17") (pintype "power_in"))
      (node (ref "P1") (pin "18") (pinfunction "M18_18") (pintype "power_in"))
      (node (ref "P1") (pin "19") (pinfunction "M19_19") (pintype "power_in"))
      (node (ref "P1") (pin "2") (pinfunction "M2_2") (pintype "power_in"))
      (node (ref "P1") (pin "20") (pinfunction "M20_20") (pintype "power_in"))
      (node (ref "P1") (pin "21") (pinfunction "M21_21") (pintype "power_in"))
      (node (ref "P1") (pin "22") (pinfunction "M22_22") (pintype "power_in"))
      (node (ref "P1") (pin "23") (pinfunction "M23_23") (pintype "power_in"))
      (node (ref "P1") (pin "24") (pinfunction "M24_24") (pintype "power_in"))
      (node (ref "P1") (pin "25") (pinfunction "M25_25") (pintype "power_in"))
      (node (ref "P1") (pin "26") (pinfunction "M26_26") (pintype "power_in"))
      (node (ref "P1") (pin "27") (pinfunction "M27_27") (pintype "power_in"))
      (node (ref "P1") (pin "28") (pinfunction "M28_28") (pintype "power_in"))
      (node (ref "P1") (pin "29") (pinfunction "M29_29") (pintype "power_in"))
      (node (ref "P1") (pin "3") (pinfunction "M3_3") (pintype "power_in"))
      (node (ref "P1") (pin "30") (pinfunction "M30_30") (pintype "power_in"))
      (node (ref "P1") (pin "31") (pinfunction "M31_31") (pintype "power_in"))
      (node (ref "P1") (pin "32") (pinfunction "M32_32") (pintype "power_in"))
      (node (ref "P1") (pin "33") (pinfunction "M33_33") (pintype "power_in"))
      (node (ref "P1") (pin "34") (pinfunction "M34_34") (pintype "power_in"))
      (node (ref "P1") (pin "4") (pinfunction "M4_4") (pintype "power_in"))
      (node (ref "P1") (pin "5") (pinfunction "M5_5") (pintype "power_in"))
      (node (ref "P1") (pin "6") (pinfunction "M6_6") (pintype "power_in"))
      (node (ref "P1") (pin "7") (pinfunction "M7_7") (pintype "power_in"))
      (node (ref "P1") (pin "8") (pinfunction "M8_8") (pintype "power_in"))
      (node (ref "P1") (pin "9") (pinfunction "M9_9") (pintype "power_in"))
      (node (ref "P1") (pin "G1") (pinfunction "G1_G1") (pintype "power_in"))
      (node (ref "P1") (pin "G2") (pinfunction "G2_G2") (pintype "power_in"))
      (node (ref "P1") (pin "G3") (pinfunction "G3_G3") (pintype "power_in"))
      (node (ref "P1") (pin "G4") (pinfunction "G4_G4") (pintype "power_in"))
      (node (ref "P2") (pin "M1") (pinfunction "M1_M1") (pintype "passive"))
      (node (ref "P2") (pin "M2") (pinfunction "M2_M2") (pintype "passive"))
      (node (ref "P3") (pin "M1") (pinfunction "M1_M1") (pintype "passive"))
      (node (ref "P3") (pin "M2") (pinfunction "M2_M2") (pintype "passive"))
      (node (ref "P4") (pin "M1") (pinfunction "M1_M1") (pintype "passive"))
      (node (ref "P4") (pin "M2") (pinfunction "M2_M2") (pintype "passive"))
      (node (ref "P5") (pin "M1") (pinfunction "M1_M1") (pintype "passive"))
      (node (ref "P5") (pin "M2") (pinfunction "M2_M2") (pintype "passive"))
      (node (ref "R19") (pin "1") (pinfunction "1_1") (pintype "passive"))
    )
    (net (code "60") (name "unconnected-(P2-Tx_Fault-Pad2)") (class "Default")
      (node (ref "P2") (pin "2") (pinfunction "Tx_Fault_2") (pintype "output+no_connect"))
    )
    (net (code "61") (name "unconnected-(P3-Tx_Fault-Pad2)") (class "Default")
      (node (ref "P3") (pin "2") (pinfunction "Tx_Fault_2") (pintype "output+no_connect"))
    )
    (net (code "62") (name "unconnected-(P4-Tx_Fault-Pad2)") (class "Default")
      (node (ref "P4") (pin "2") (pinfunction "Tx_Fault_2") (pintype "output+no_connect"))
    )
    (net (code "63") (name "unconnected-(P5-Tx_Fault-Pad2)") (class "Default")
      (node (ref "P5") (pin "2") (pinfunction "Tx_Fault_2") (pintype "output+no_connect"))
    )
  )
)
